# DCCRegulator.net
KiCad netlist of a schematic drawn in Altium Designer
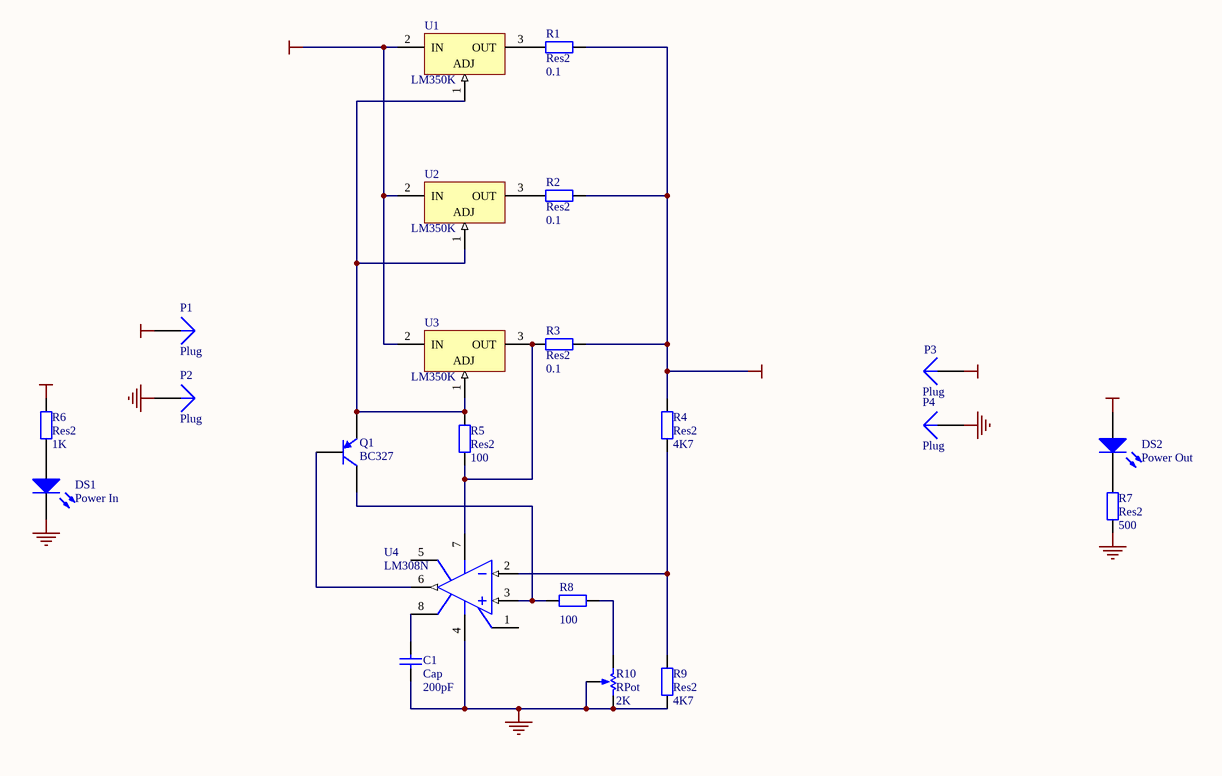
[diagram p0: DCCRegulator.SchDoc]

(export (version "E")
  (design (tool "Eeschema 10.0.6"))
  (components
    (comp (ref "C1")
      (value "Cap")
      (footprint "RAD-0.2")
      (description "Capacitor")
      (fields (field (name "ALTIUM_VALUE") "200pF") (field (name "PUBLISHER") "Altium Limited"))
      (libsource (lib "Miscellaneous Devices") (part "Cap"))
    )
    (comp (ref "DS1")
      (value "Power In")
      (footprint "LED5mm")
      (description "Typical INFRARED GaAs LED")
      (fields (field (name "PUBLISHER") "Altium Limited"))
      (libsource (lib "Miscellaneous Devices") (part "LED0"))
    )
    (comp (ref "DS2")
      (value "Power Out")
      (footprint "LED5mm")
      (description "Typical INFRARED GaAs LED")
      (fields (field (name "PUBLISHER") "Altium Limited"))
      (libsource (lib "Miscellaneous Devices") (part "LED0"))
    )
    (comp (ref "P1")
      (value "Plug")
      (footprint "PIN1")
      (fields (field (name "PUBLISHER") "Altium Limited"))
      (libsource (lib "Miscellaneous Connectors") (part "Plug"))
    )
    (comp (ref "P2")
      (value "Plug")
      (footprint "PIN1")
      (fields (field (name "PUBLISHER") "Altium Limited"))
      (libsource (lib "Miscellaneous Connectors") (part "Plug"))
    )
    (comp (ref "P3")
      (value "Plug")
      (footprint "PIN1")
      (fields (field (name "PUBLISHER") "Altium Limited"))
      (libsource (lib "Miscellaneous Connectors") (part "Plug"))
    )
    (comp (ref "P4")
      (value "Plug")
      (footprint "PIN1")
      (fields (field (name "PUBLISHER") "Altium Limited"))
      (libsource (lib "Miscellaneous Connectors") (part "Plug"))
    )
    (comp (ref "Q1")
      (value "BC327")
      (footprint "29-04")
      (description "Amplifier Transistor PNP Silicon")
      (fields (field (name "PUBLISHER") "Altium Limited"))
      (libsource (lib "Motorola Discrete BJT") (part "BC327"))
    )
    (comp (ref "R1")
      (value "Res2")
      (footprint "AXIAL-1.0")
      (description "Resistor")
      (fields (field (name "ALTIUM_VALUE") "0.1") (field (name "PUBLISHER") "Altium Limited"))
      (libsource (lib "") (part "Res2_2"))
    )
    (comp (ref "R2")
      (value "Res2")
      (footprint "AXIAL-1.0")
      (description "Resistor")
      (fields (field (name "ALTIUM_VALUE") "0.1") (field (name "PUBLISHER") "Altium Limited"))
      (libsource (lib "") (part "Res2_2"))
    )
    (comp (ref "R3")
      (value "Res2")
      (footprint "AXIAL-1.0")
      (description "Resistor")
      (fields (field (name "ALTIUM_VALUE") "0.1") (field (name "PUBLISHER") "Altium Limited"))
      (libsource (lib "") (part "Res2_2"))
    )
    (comp (ref "R4")
      (value "Res2")
      (footprint "AXIAL-0.3")
      (description "Resistor")
      (fields (field (name "ALTIUM_VALUE") "4K7") (field (name "PUBLISHER") "Altium Limited"))
      (libsource (lib "Miscellaneous Devices") (part "Res2"))
    )
    (comp (ref "R5")
      (value "Res2")
      (footprint "AXIAL-0.3")
      (description "Resistor")
      (fields (field (name "ALTIUM_VALUE") "100") (field (name "PUBLISHER") "Altium Limited"))
      (libsource (lib "Miscellaneous Devices") (part "Res2"))
    )
    (comp (ref "R6")
      (value "Res2")
      (footprint "AXIAL-0.3")
      (description "Resistor")
      (fields (field (name "ALTIUM_VALUE") "1K") (field (name "PUBLISHER") "Altium Limited"))
      (libsource (lib "Miscellaneous Devices") (part "Res2"))
    )
    (comp (ref "R7")
      (value "Res2")
      (footprint "AXIAL-0.3")
      (description "Resistor")
      (fields (field (name "ALTIUM_VALUE") "500") (field (name "PUBLISHER") "Altium Limited"))
      (libsource (lib "Miscellaneous Devices") (part "Res2"))
    )
    (comp (ref "R8")
      (value "100")
      (footprint "AXIAL-0.3")
      (description "Resistor")
      (fields (field (name "Comment") "Res2") (field (name "PUBLISHER") "Altium Limited"))
      (libsource (lib "") (part "Res2_1"))
    )
    (comp (ref "R9")
      (value "Res2")
      (footprint "AXIAL-0.3")
      (description "Resistor")
      (fields (field (name "ALTIUM_VALUE") "4K7") (field (name "PUBLISHER") "Altium Limited"))
      (libsource (lib "Miscellaneous Devices") (part "Res2"))
    )
    (comp (ref "R10")
      (value "RPot")
      (footprint "Horizontal Trim Pot")
      (description "Potentiometer")
      (fields (field (name "ALTIUM_VALUE") "2K") (field (name "PUBLISHER") "Altium Limited"))
      (libsource (lib "Miscellaneous Devices") (part "RPot"))
    )
    (comp (ref "U1")
      (value "LM350K")
      (footprint "1-03")
      (description "3-Terminal Adjustable Positive Voltage Regulator")
      (fields (field (name "PUBLISHER") "Altium Limited"))
      (libsource (lib "Motorola Power Mgt Voltage Regulator") (part "LM350K"))
    )
    (comp (ref "U2")
      (value "LM350K")
      (footprint "1-03")
      (description "3-Terminal Adjustable Positive Voltage Regulator")
      (fields (field (name "PUBLISHER") "Altium Limited"))
      (libsource (lib "Motorola Power Mgt Voltage Regulator") (part "LM350K"))
    )
    (comp (ref "U3")
      (value "LM350K")
      (footprint "1-03")
      (description "3-Terminal Adjustable Positive Voltage Regulator")
      (fields (field (name "PUBLISHER") "Altium Limited"))
      (libsource (lib "Motorola Power Mgt Voltage Regulator") (part "LM350K"))
    )
    (comp (ref "U4")
      (value "LM308N")
      (footprint "626-05")
      (description "Precision Operational Amplifier")
      (fields (field (name "PUBLISHER") "Altium Limited"))
      (libsource (lib "Motorola Amplifier Operational Amplifier") (part "LM308N"))
    )
  )
  (nets
    (net (code "1") (name "GND") (class "Default")
      (node (ref "C1") (pin "1") (pinfunction "1_1") (pintype "passive"))
      (node (ref "DS1") (pin "2") (pinfunction "K_2") (pintype "passive"))
      (node (ref "P2") (pin "1") (pinfunction "1_1") (pintype "passive"))
      (node (ref "P4") (pin "1") (pinfunction "1_1") (pintype "passive"))
      (node (ref "R10") (pin "1") (pinfunction "TOP_1") (pintype "passive"))
      (node (ref "R10") (pin "3") (pinfunction "TAP_3") (pintype "passive"))
      (node (ref "R7") (pin "1") (pinfunction "1_1") (pintype "passive"))
      (node (ref "R9") (pin "1") (pinfunction "1_1") (pintype "passive"))
      (node (ref "U4") (pin "4") (pinfunction "V-_4") (pintype "power_in"))
    )
    (net (code "2") (name "Net-(DS1-A)") (class "Default")
      (node (ref "DS1") (pin "1") (pinfunction "A_1") (pintype "passive"))
      (node (ref "R6") (pin "1") (pinfunction "1_1") (pintype "passive"))
    )
    (net (code "3") (name "Net-(DS2-K)") (class "Default")
      (node (ref "DS2") (pin "2") (pinfunction "K_2") (pintype "passive"))
      (node (ref "R7") (pin "2") (pinfunction "2_2") (pintype "passive"))
    )
    (net (code "4") (name "Net-(Q1-B)") (class "Default")
      (node (ref "Q1") (pin "2") (pinfunction "B_2") (pintype "passive"))
      (node (ref "U4") (pin "6") (pinfunction "OUT_6") (pintype "output"))
    )
    (net (code "5") (name "Net-(Q1-C)") (class "Default")
      (node (ref "Q1") (pin "1") (pinfunction "C_1") (pintype "passive"))
      (node (ref "R8") (pin "2") (pinfunction "2_2") (pintype "passive"))
      (node (ref "U4") (pin "3") (pinfunction "IN+_3") (pintype "input"))
    )
    (net (code "6") (name "Net-(Q1-E)") (class "Default")
      (node (ref "Q1") (pin "3") (pinfunction "E_3") (pintype "passive"))
      (node (ref "R5") (pin "2") (pinfunction "2_2") (pintype "passive"))
      (node (ref "U1") (pin "1") (pinfunction "ADJ_1") (pintype "input"))
      (node (ref "U2") (pin "1") (pinfunction "ADJ_1") (pintype "input"))
      (node (ref "U3") (pin "1") (pinfunction "ADJ_1") (pintype "input"))
    )
    (net (code "7") (name "Net-(R10-BOT)") (class "Default")
      (node (ref "R10") (pin "2") (pinfunction "BOT_2") (pintype "passive"))
      (node (ref "R8") (pin "1") (pinfunction "1_1") (pintype "passive"))
    )
    (net (code "8") (name "Net-(U1-OUT)") (class "Default")
      (node (ref "R1") (pin "1") (pinfunction "1_1") (pintype "passive"))
      (node (ref "U1") (pin "3") (pinfunction "OUT_3") (pintype "power_in"))
    )
    (net (code "9") (name "Net-(U2-OUT)") (class "Default")
      (node (ref "R2") (pin "1") (pinfunction "1_1") (pintype "passive"))
      (node (ref "U2") (pin "3") (pinfunction "OUT_3") (pintype "power_in"))
    )
    (net (code "10") (name "Net-(U3-OUT)") (class "Default")
      (node (ref "R3") (pin "1") (pinfunction "1_1") (pintype "passive"))
      (node (ref "R5") (pin "1") (pinfunction "1_1") (pintype "passive"))
      (node (ref "U3") (pin "3") (pinfunction "OUT_3") (pintype "power_in"))
      (node (ref "U4") (pin "7") (pinfunction "V+_7") (pintype "power_in"))
    )
    (net (code "11") (name "Net-(U4-CMPEN_2)") (class "Default")
      (node (ref "C1") (pin "2") (pinfunction "2_2") (pintype "passive"))
      (node (ref "U4") (pin "8") (pinfunction "CMPEN_2_8") (pintype "passive"))
    )
    (net (code "12") (name "Net-(U4-IN-)") (class "Default")
      (node (ref "R4") (pin "1") (pinfunction "1_1") (pintype "passive"))
      (node (ref "R9") (pin "2") (pinfunction "2_2") (pintype "passive"))
      (node (ref "U4") (pin "2") (pinfunction "IN-_2") (pintype "input"))
    )
    (net (code "13") (name "Vin") (class "Default")
      (node (ref "P1") (pin "1") (pinfunction "1_1") (pintype "passive"))
      (node (ref "R6") (pin "2") (pinfunction "2_2") (pintype "passive"))
      (node (ref "U1") (pin "2") (pinfunction "IN_2") (pintype "power_in"))
      (node (ref "U2") (pin "2") (pinfunction "IN_2") (pintype "power_in"))
      (node (ref "U3") (pin "2") (pinfunction "IN_2") (pintype "power_in"))
    )
    (net (code "14") (name "Vout") (class "Default")
      (node (ref "DS2") (pin "1") (pinfunction "A_1") (pintype "passive"))
      (node (ref "P3") (pin "1") (pinfunction "1_1") (pintype "passive"))
      (node (ref "R1") (pin "2") (pinfunction "2_2") (pintype "passive"))
      (node (ref "R2") (pin "2") (pinfunction "2_2") (pintype "passive"))
      (node (ref "R3") (pin "2") (pinfunction "2_2") (pintype "passive"))
      (node (ref "R4") (pin "2") (pinfunction "2_2") (pintype "passive"))
    )
    (net (code "15") (name "unconnected-(U4-CMPEN_1-Pad1)") (class "Default")
      (node (ref "U4") (pin "1") (pinfunction "CMPEN_1_1") (pintype "passive"))
    )
    (net (code "16") (name "unconnected-(U4-NC-Pad5)") (class "Default")
      (node (ref "U4") (pin "5") (pinfunction "NC_5") (pintype "passive"))
    )
  )
)
